# io.net
KiCad netlist of a schematic drawn in EAGLE
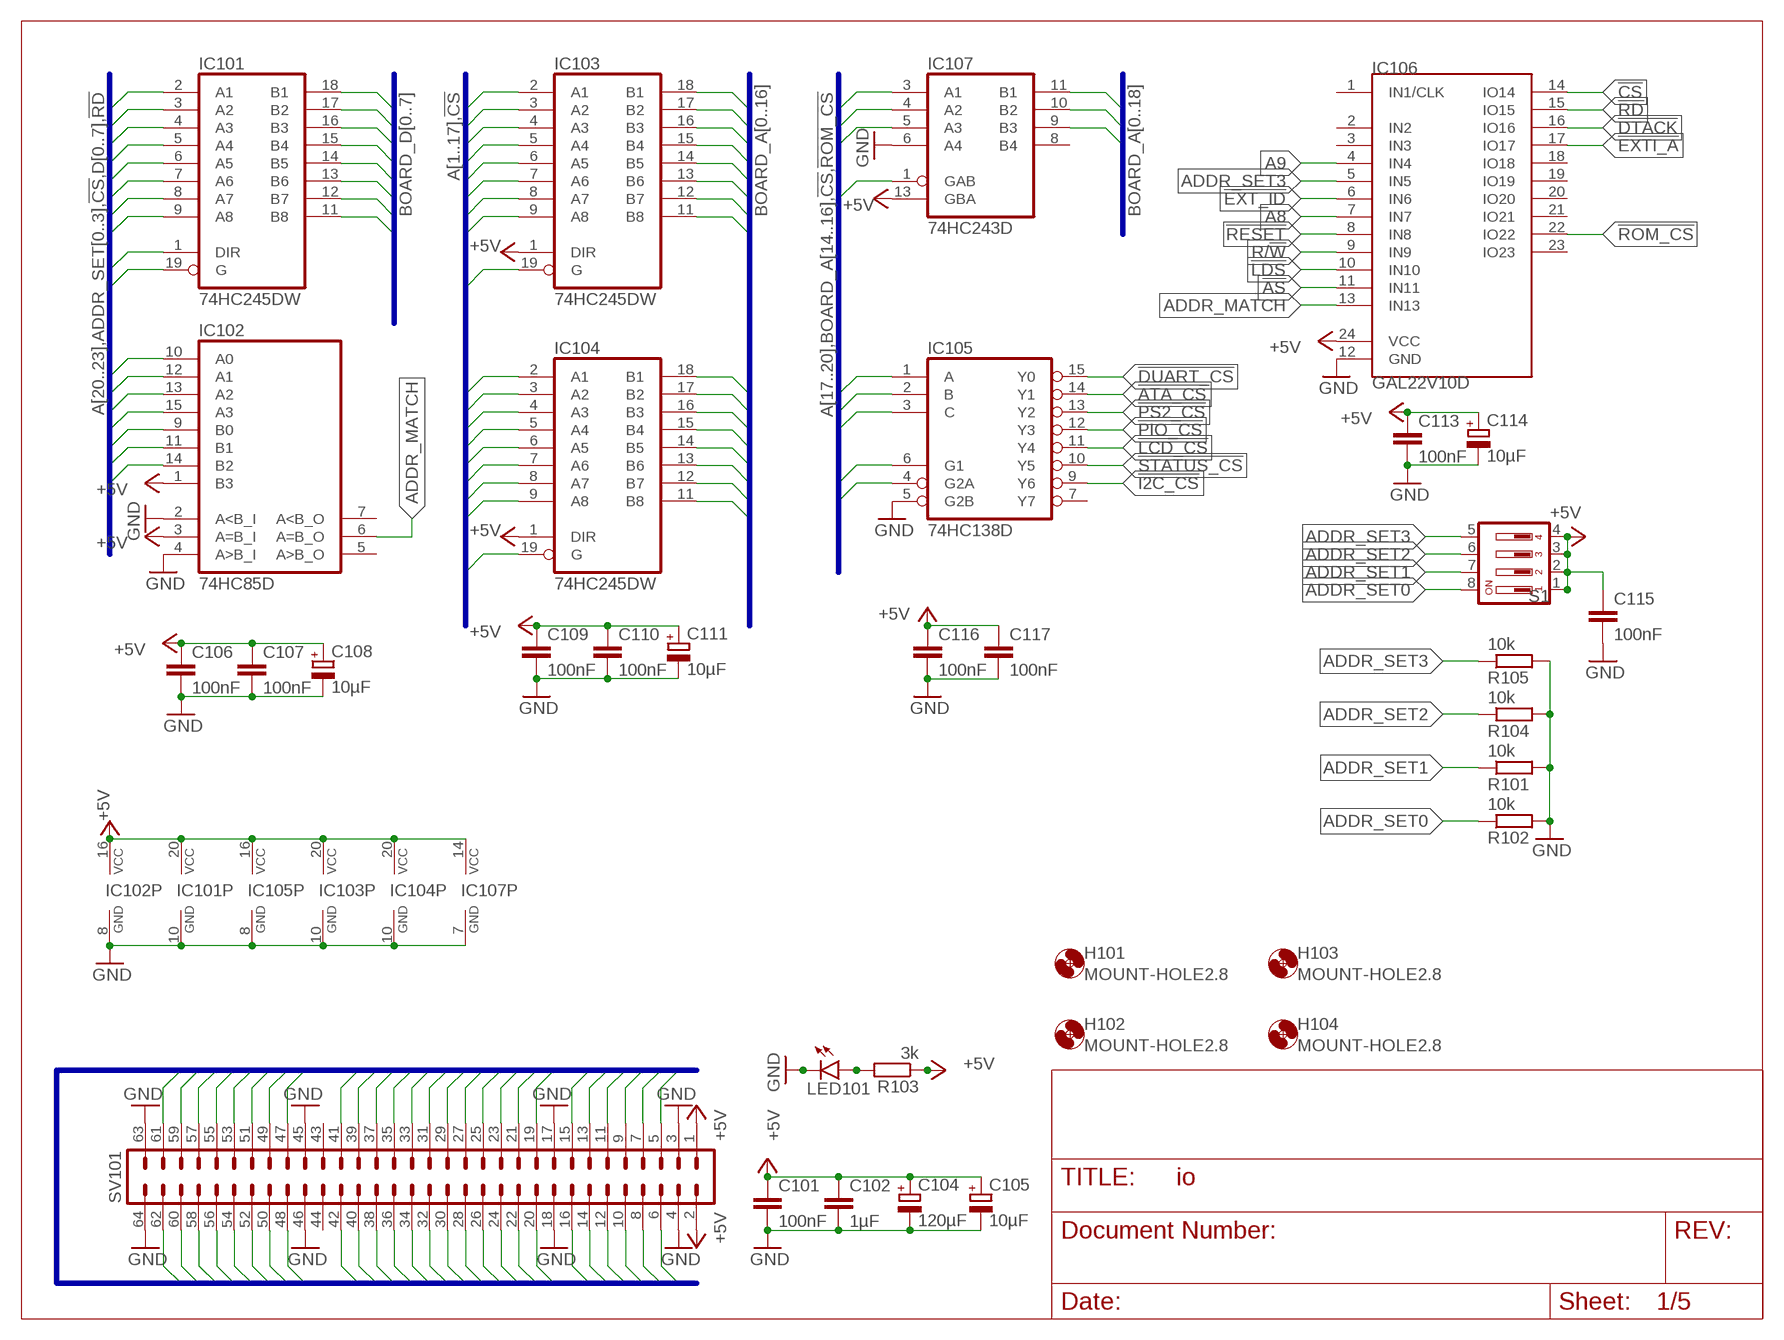
[diagram p0: schematic, sheet 1]
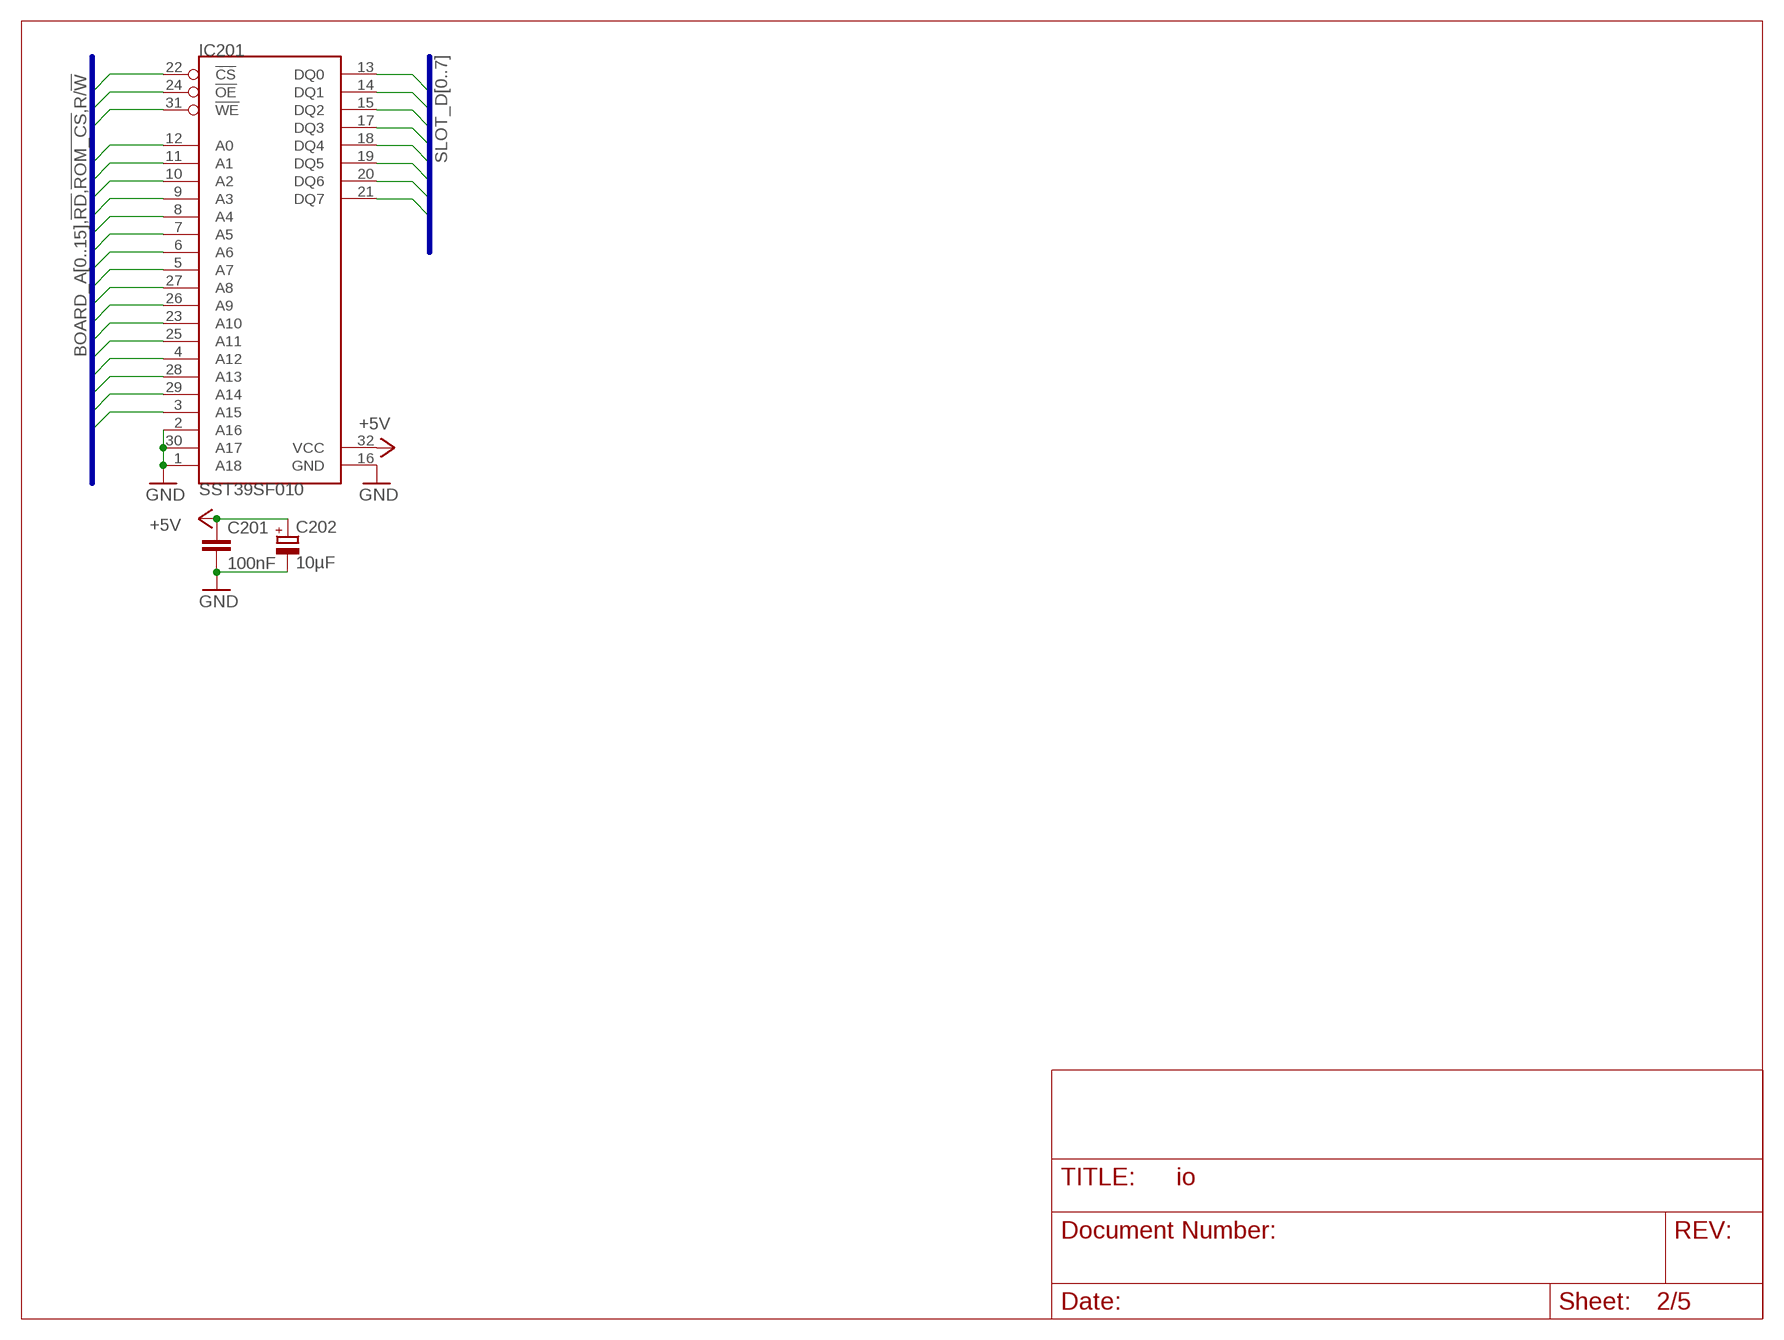
[diagram p1: schematic, sheet 2]
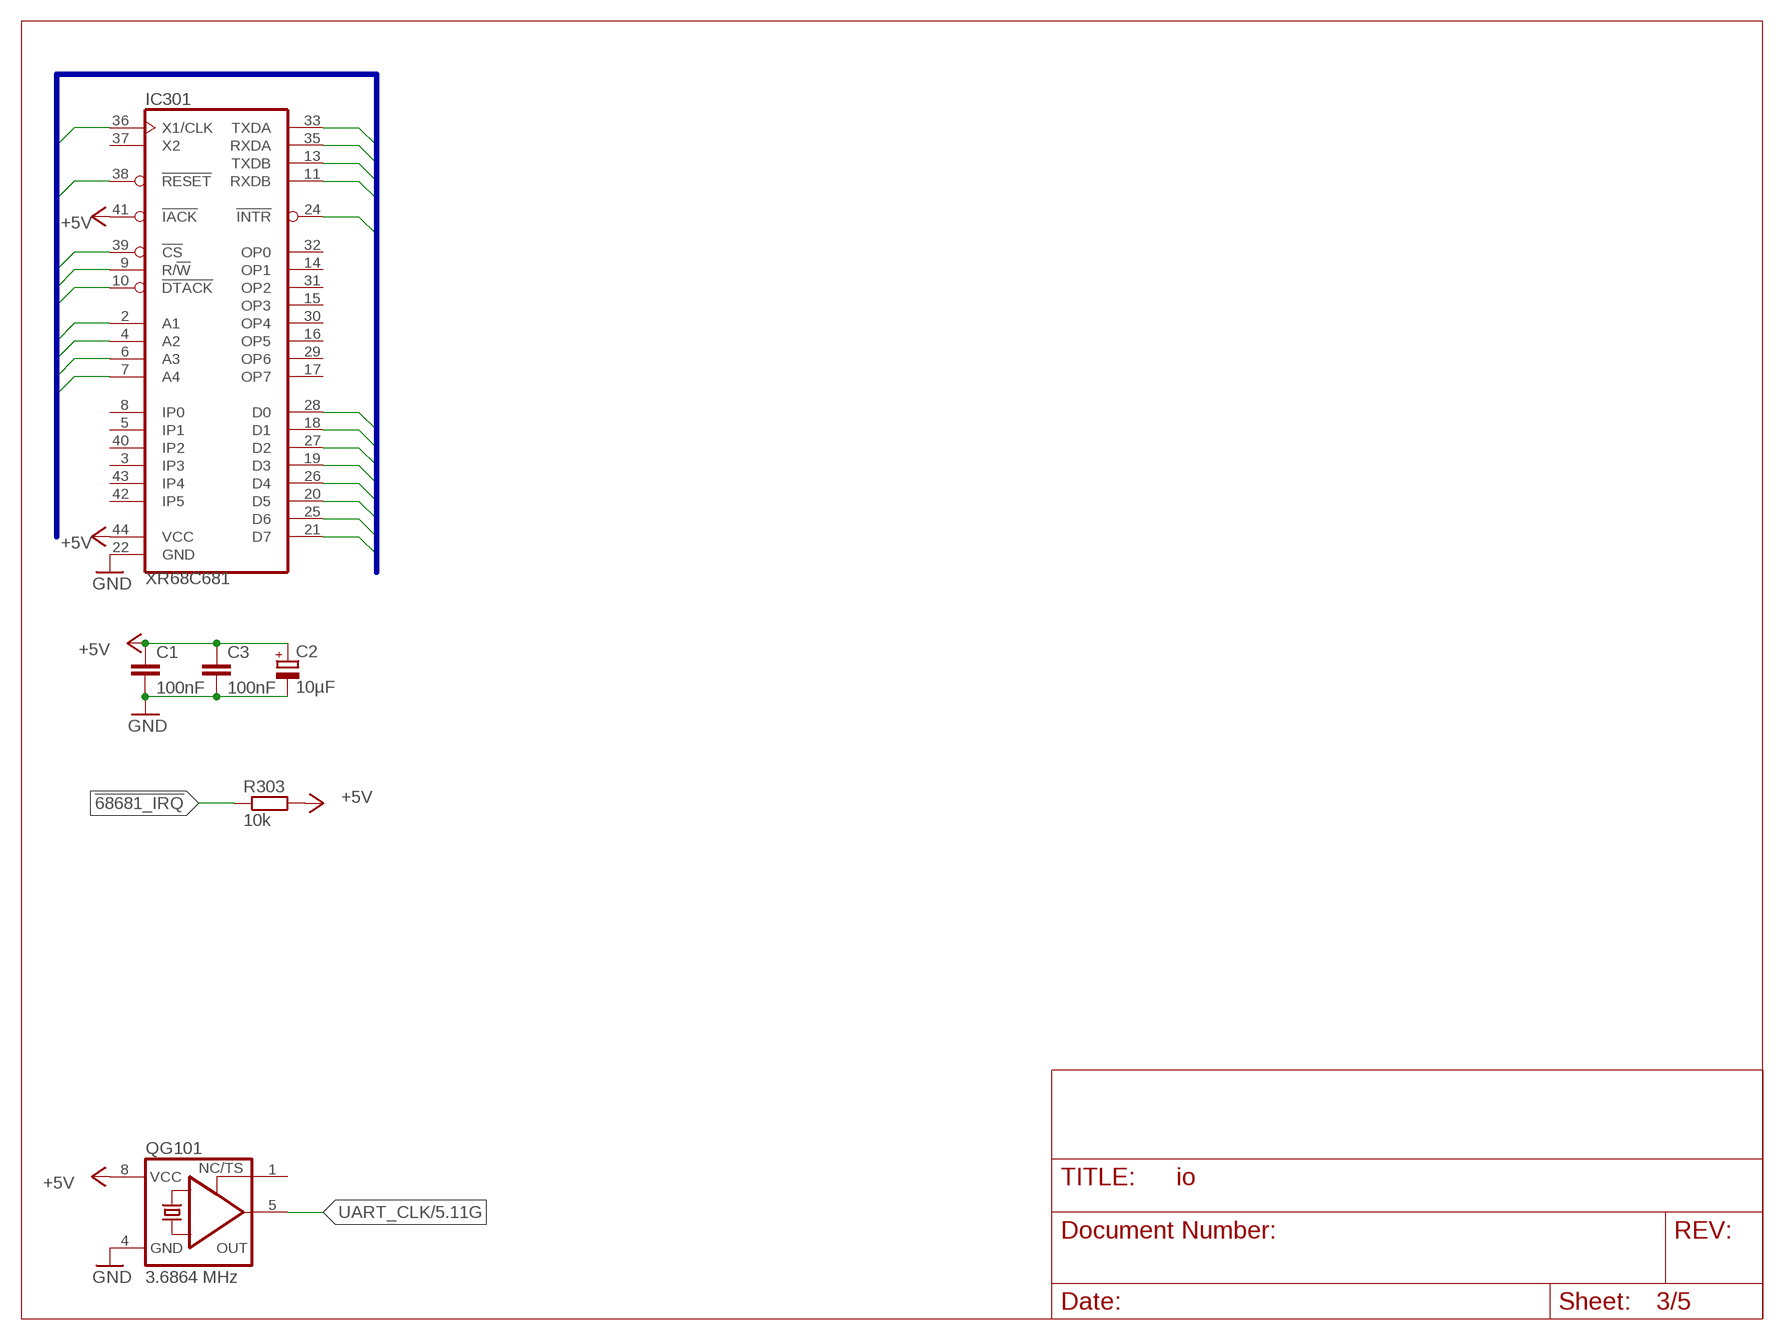
[diagram p2: schematic, sheet 3]
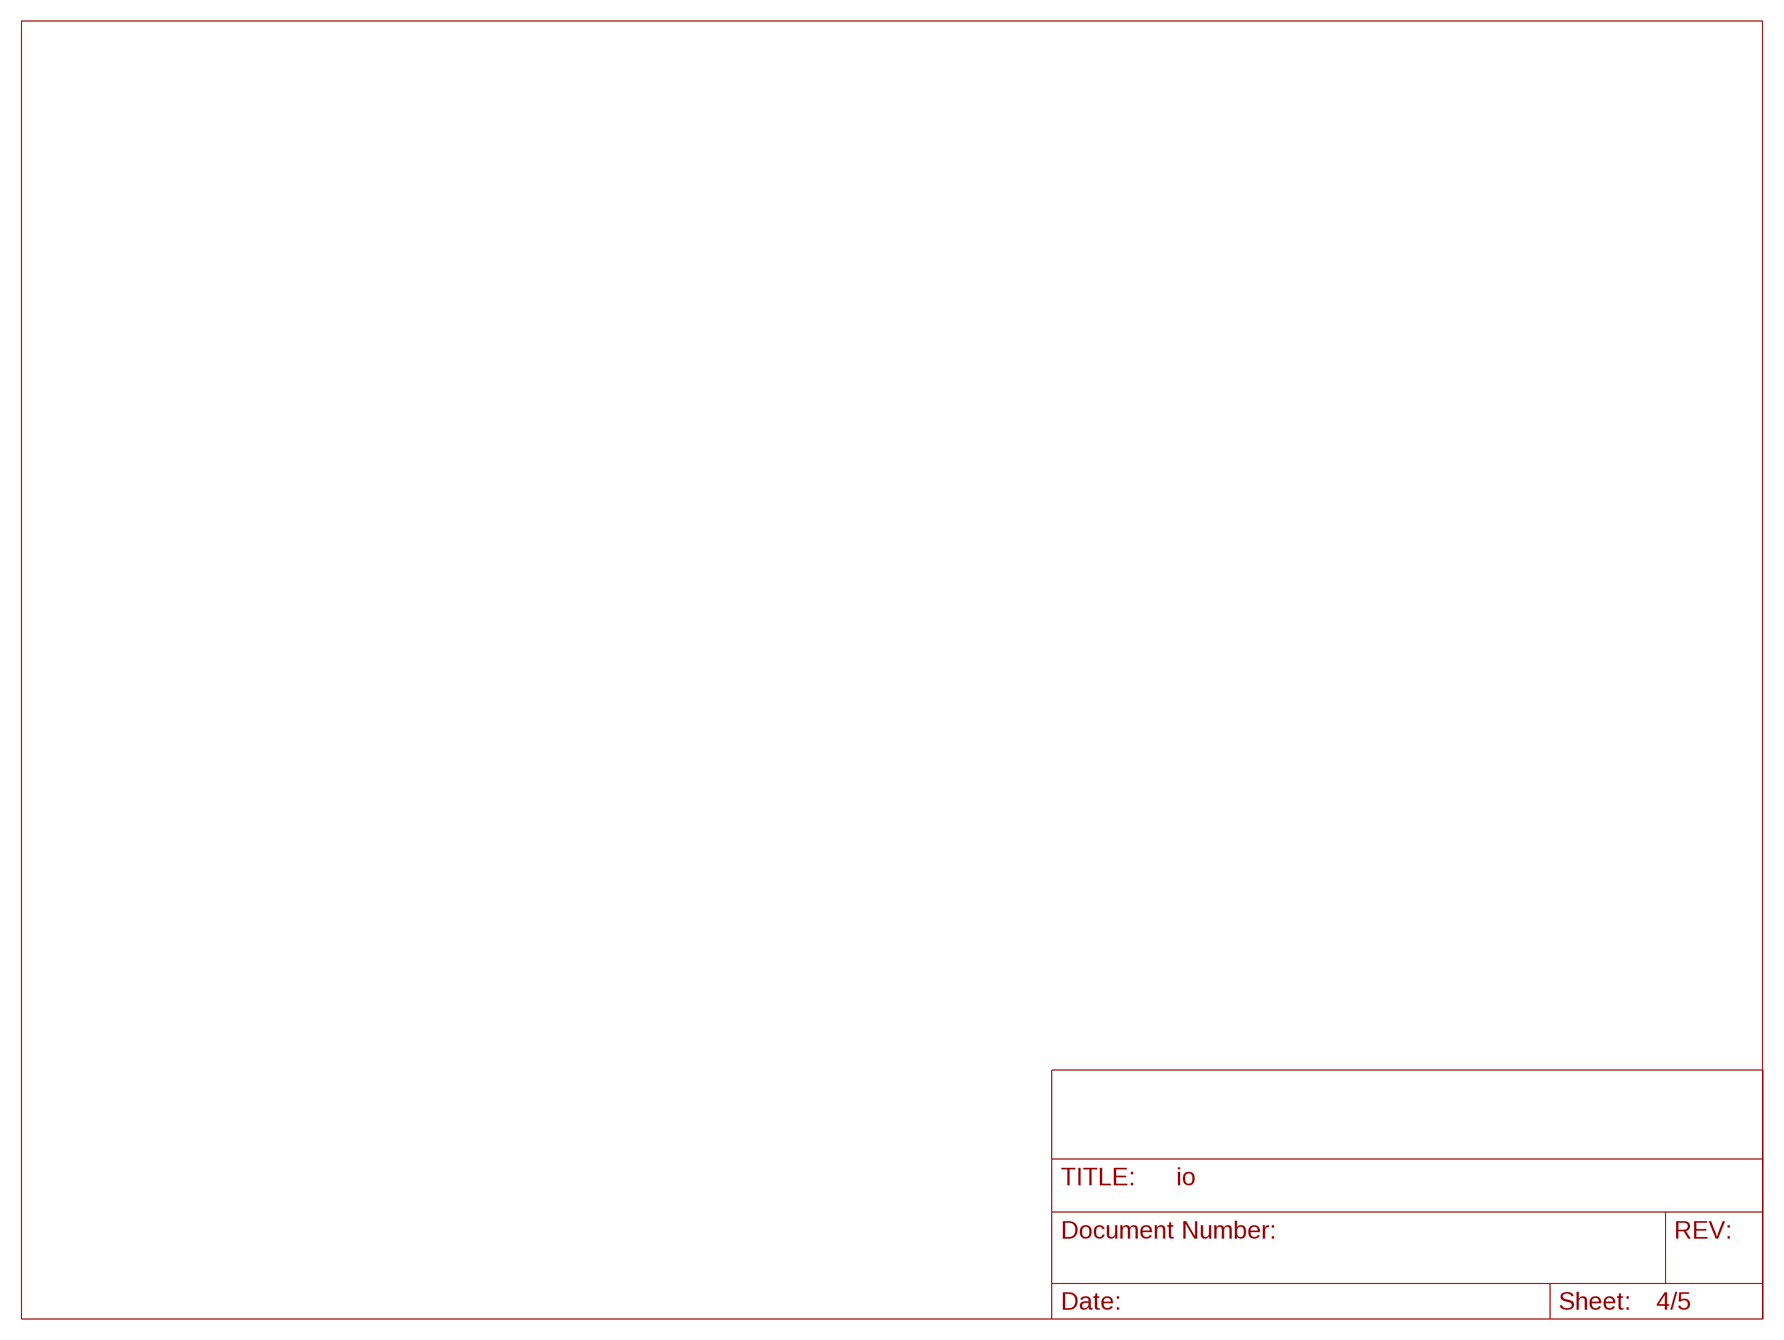
[diagram p3: schematic, sheet 4]
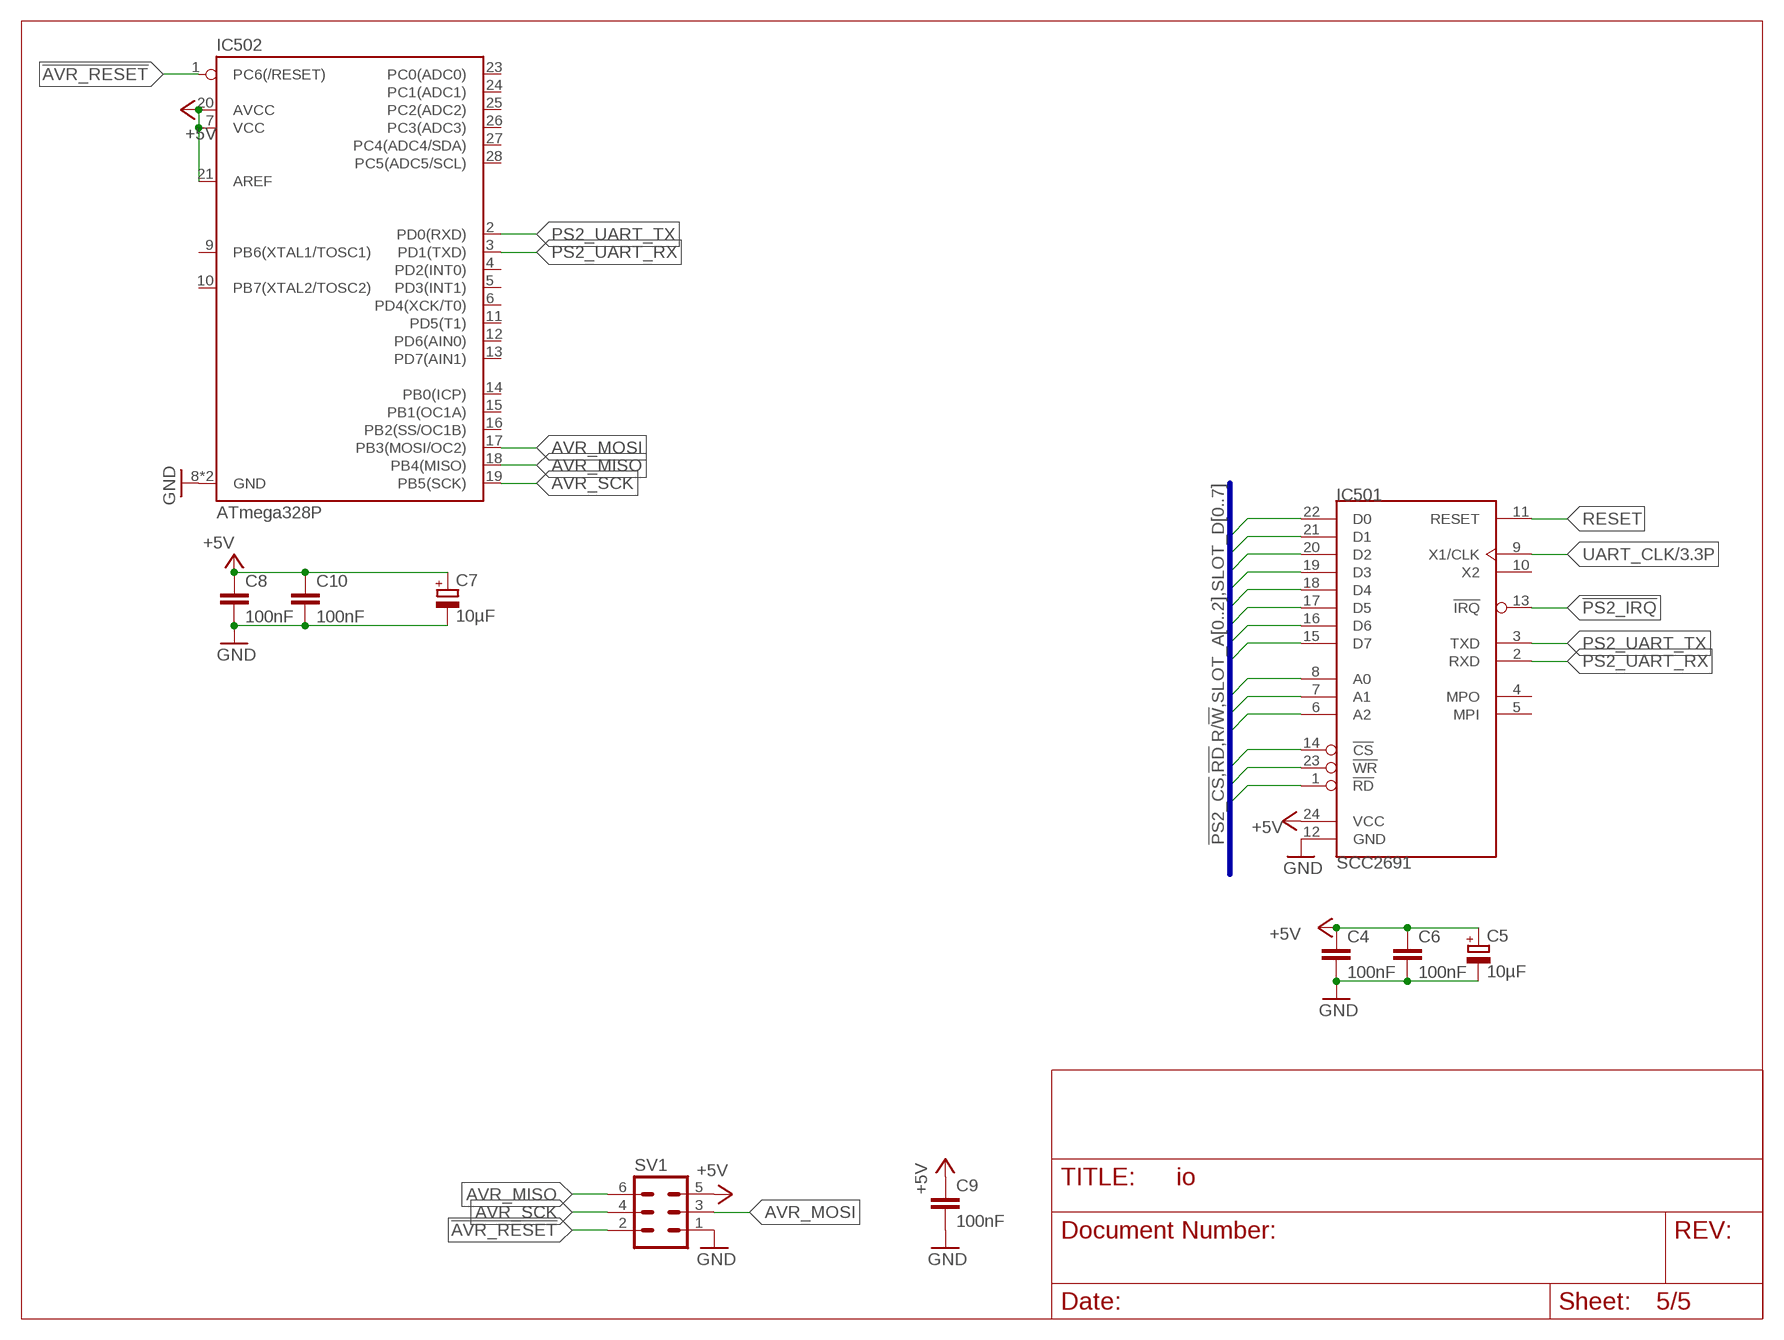
[diagram p4: schematic, sheet 5]

(export (version "E")
  (design (tool "Eeschema 10.0.6"))
  (components
    (comp (ref "C1")
      (value "100nF")
      (footprint "eagle-import:C0805")
      (libsource (lib "eagle-import") (part "C-EUC0805"))
    )
    (comp (ref "C2")
      (value "10µF")
      (footprint "eagle-import:SMC_B")
      (libsource (lib "eagle-import") (part "CPOL-EUSMCB"))
    )
    (comp (ref "C3")
      (value "100nF")
      (footprint "eagle-import:C0805")
      (libsource (lib "eagle-import") (part "C-EUC0805"))
    )
    (comp (ref "IC301")
      (value "XR68C681")
      (footprint "eagle-import:PLCC-S44")
      (libsource (lib "eagle-import") (part "MC68681PLCC44-SOCKET"))
    )
    (comp (ref "QG101")
      (value "3.6864 MHz")
      (footprint "eagle-import:DIL08S")
      (libsource (lib "eagle-import") (part "XO-8"))
    )
    (comp (ref "R303")
      (value "10k")
      (footprint "eagle-import:R2012")
      (libsource (lib "eagle-import") (part "R-EU_R2012"))
    )
    (comp (ref "C101")
      (value "100nF")
      (footprint "eagle-import:C0805")
      (libsource (lib "eagle-import") (part "C-EUC0805"))
    )
    (comp (ref "C102")
      (value "1µF")
      (footprint "eagle-import:C0805")
      (libsource (lib "eagle-import") (part "C-EUC0805"))
    )
    (comp (ref "C104")
      (value "120µF")
      (footprint "eagle-import:E2,5-7")
      (libsource (lib "eagle-import") (part "CPOL-EUE2.5-7"))
    )
    (comp (ref "C105")
      (value "10µF")
      (footprint "eagle-import:SMC_B")
      (libsource (lib "eagle-import") (part "CPOL-EUSMCB"))
    )
    (comp (ref "C106")
      (value "100nF")
      (footprint "eagle-import:C0805")
      (libsource (lib "eagle-import") (part "C-EUC0805"))
    )
    (comp (ref "C107")
      (value "100nF")
      (footprint "eagle-import:C0805")
      (libsource (lib "eagle-import") (part "C-EUC0805"))
    )
    (comp (ref "C108")
      (value "10µF")
      (footprint "eagle-import:SMC_B")
      (libsource (lib "eagle-import") (part "CPOL-EUSMCB"))
    )
    (comp (ref "C109")
      (value "100nF")
      (footprint "eagle-import:C0805")
      (libsource (lib "eagle-import") (part "C-EUC0805"))
    )
    (comp (ref "C110")
      (value "100nF")
      (footprint "eagle-import:C0805")
      (libsource (lib "eagle-import") (part "C-EUC0805"))
    )
    (comp (ref "C111")
      (value "10µF")
      (footprint "eagle-import:SMC_B")
      (libsource (lib "eagle-import") (part "CPOL-EUSMCB"))
    )
    (comp (ref "C113")
      (value "100nF")
      (footprint "eagle-import:C0805")
      (libsource (lib "eagle-import") (part "C-EUC0805"))
    )
    (comp (ref "C114")
      (value "10µF")
      (footprint "eagle-import:SMC_B")
      (libsource (lib "eagle-import") (part "CPOL-EUSMCB"))
    )
    (comp (ref "C115")
      (value "100nF")
      (footprint "eagle-import:C0805")
      (libsource (lib "eagle-import") (part "C-EUC0805"))
    )
    (comp (ref "C116")
      (value "100nF")
      (footprint "eagle-import:C0805")
      (libsource (lib "eagle-import") (part "C-EUC0805"))
    )
    (comp (ref "C117")
      (value "100nF")
      (footprint "eagle-import:C0805")
      (libsource (lib "eagle-import") (part "C-EUC0805"))
    )
    (comp (ref "H101")
      (value "MOUNT-HOLE2.8")
      (footprint "eagle-import:2,8")
      (libsource (lib "eagle-import") (part "MOUNT-HOLE2.8"))
    )
    (comp (ref "H102")
      (value "MOUNT-HOLE2.8")
      (footprint "eagle-import:2,8")
      (libsource (lib "eagle-import") (part "MOUNT-HOLE2.8"))
    )
    (comp (ref "H103")
      (value "MOUNT-HOLE2.8")
      (footprint "eagle-import:2,8")
      (libsource (lib "eagle-import") (part "MOUNT-HOLE2.8"))
    )
    (comp (ref "H104")
      (value "MOUNT-HOLE2.8")
      (footprint "eagle-import:2,8")
      (libsource (lib "eagle-import") (part "MOUNT-HOLE2.8"))
    )
    (comp (ref "IC101")
      (value "74HC245DW")
      (footprint "eagle-import:SO20W")
      (fields (field (name "MOUSER") "595-SN74HC245DWR"))
      (libsource (lib "eagle-import") (part "74245DWHC"))
    )
    (comp (ref "IC102")
      (value "74HC85D")
      (footprint "eagle-import:SO16")
      (fields (field (name "MOUSER") "771-74HC138D"))
      (libsource (lib "eagle-import") (part "7485DHC"))
    )
    (comp (ref "IC103")
      (value "74HC245DW")
      (footprint "eagle-import:SO20W")
      (fields (field (name "MOUSER") "595-SN74HC245DWR"))
      (libsource (lib "eagle-import") (part "74245DWHC"))
    )
    (comp (ref "IC104")
      (value "74HC245DW")
      (footprint "eagle-import:SO20W")
      (fields (field (name "MOUSER") "595-SN74HC245DWR"))
      (libsource (lib "eagle-import") (part "74245DWHC"))
    )
    (comp (ref "IC105")
      (value "74HC138D")
      (footprint "eagle-import:SO16")
      (fields (field (name "MOUSER") "771-74HC138D"))
      (libsource (lib "eagle-import") (part "74138DHC"))
    )
    (comp (ref "IC106")
      (value "GAL22V10D")
      (footprint "eagle-import:DIL24S")
      (libsource (lib "eagle-import") (part "GAL22V10DIP24"))
    )
    (comp (ref "IC107")
      (value "74HC243D")
      (footprint "eagle-import:SO14")
      (fields (field (name "MOUSER") "595-CD74HC243M96"))
      (libsource (lib "eagle-import") (part "74243DHC"))
    )
    (comp (ref "LED101")
      (value "LEDCHIPLED_1206")
      (footprint "eagle-import:CHIPLED_1206")
      (libsource (lib "eagle-import") (part "LEDCHIPLED_1206"))
    )
    (comp (ref "R101")
      (value "10k")
      (footprint "eagle-import:R2012")
      (libsource (lib "eagle-import") (part "R-EU_R2012"))
    )
    (comp (ref "R102")
      (value "10k")
      (footprint "eagle-import:R2012")
      (libsource (lib "eagle-import") (part "R-EU_R2012"))
    )
    (comp (ref "R103")
      (value "3k")
      (footprint "eagle-import:R2012")
      (libsource (lib "eagle-import") (part "R-EU_R2012"))
    )
    (comp (ref "R104")
      (value "10k")
      (footprint "eagle-import:R2012")
      (libsource (lib "eagle-import") (part "R-EU_R2012"))
    )
    (comp (ref "R105")
      (value "10k")
      (footprint "eagle-import:R2012")
      (libsource (lib "eagle-import") (part "R-EU_R2012"))
    )
    (comp (ref "S1")
      (value "DP04")
      (footprint "eagle-import:DP-04")
      (libsource (lib "eagle-import") (part "DP04"))
    )
    (comp (ref "SV101")
      (value "ML64L")
      (footprint "eagle-import:ML64L")
      (libsource (lib "eagle-import") (part "ML64L"))
    )
    (comp (ref "C201")
      (value "100nF")
      (footprint "eagle-import:C0805")
      (libsource (lib "eagle-import") (part "C-EUC0805"))
    )
    (comp (ref "C202")
      (value "10µF")
      (footprint "eagle-import:SMC_B")
      (libsource (lib "eagle-import") (part "CPOL-EUSMCB"))
    )
    (comp (ref "IC201")
      (value "SST39SF010")
      (footprint "eagle-import:PLCC-S32")
      (libsource (lib "eagle-import") (part "SST39SF0X0PLCC32-SOCKET"))
    )
    (comp (ref "C4")
      (value "100nF")
      (footprint "eagle-import:C0805")
      (libsource (lib "eagle-import") (part "C-EUC0805"))
    )
    (comp (ref "C5")
      (value "10µF")
      (footprint "eagle-import:SMC_B")
      (libsource (lib "eagle-import") (part "CPOL-EUSMCB"))
    )
    (comp (ref "C6")
      (value "100nF")
      (footprint "eagle-import:C0805")
      (libsource (lib "eagle-import") (part "C-EUC0805"))
    )
    (comp (ref "C7")
      (value "10µF")
      (footprint "eagle-import:SMC_B")
      (libsource (lib "eagle-import") (part "CPOL-EUSMCB"))
    )
    (comp (ref "C8")
      (value "100nF")
      (footprint "eagle-import:C0805")
      (libsource (lib "eagle-import") (part "C-EUC0805"))
    )
    (comp (ref "C9")
      (value "100nF")
      (footprint "eagle-import:C0805")
      (libsource (lib "eagle-import") (part "C-EUC0805"))
    )
    (comp (ref "C10")
      (value "100nF")
      (footprint "eagle-import:C0805")
      (libsource (lib "eagle-import") (part "C-EUC0805"))
    )
    (comp (ref "IC501")
      (value "SCC2691")
      (footprint "eagle-import:DIL24S")
      (libsource (lib "eagle-import") (part "SCC2691"))
    )
    (comp (ref "IC502")
      (value "ATmega328P")
      (footprint "eagle-import:DIP28")
      (libsource (lib "eagle-import") (part "ATMEGA328P_PDIP"))
    )
    (comp (ref "SV1")
      (value "ML6")
      (footprint "eagle-import:ML6")
      (libsource (lib "eagle-import") (part "ML6"))
    )
  )
  (nets
    (net (code "3") (name "+5V") (class "Default")
      (node (ref "C1") (pin "1") (pinfunction "1_1") (pintype "passive"))
      (node (ref "C10") (pin "1") (pinfunction "1_1") (pintype "passive"))
      (node (ref "C101") (pin "1") (pinfunction "1_1") (pintype "passive"))
      (node (ref "C102") (pin "1") (pinfunction "1_1") (pintype "passive"))
      (node (ref "C104") (pin "+") (pinfunction "+_+") (pintype "passive"))
      (node (ref "C105") (pin "+") (pinfunction "+_+") (pintype "passive"))
      (node (ref "C106") (pin "1") (pinfunction "1_1") (pintype "passive"))
      (node (ref "C107") (pin "1") (pinfunction "1_1") (pintype "passive"))
      (node (ref "C108") (pin "+") (pinfunction "+_+") (pintype "passive"))
      (node (ref "C109") (pin "1") (pinfunction "1_1") (pintype "passive"))
      (node (ref "C110") (pin "1") (pinfunction "1_1") (pintype "passive"))
      (node (ref "C111") (pin "+") (pinfunction "+_+") (pintype "passive"))
      (node (ref "C113") (pin "1") (pinfunction "1_1") (pintype "passive"))
      (node (ref "C114") (pin "+") (pinfunction "+_+") (pintype "passive"))
      (node (ref "C115") (pin "1") (pinfunction "1_1") (pintype "passive"))
      (node (ref "C116") (pin "1") (pinfunction "1_1") (pintype "passive"))
      (node (ref "C117") (pin "1") (pinfunction "1_1") (pintype "passive"))
      (node (ref "C2") (pin "+") (pinfunction "+_+") (pintype "passive"))
      (node (ref "C201") (pin "1") (pinfunction "1_1") (pintype "passive"))
      (node (ref "C202") (pin "+") (pinfunction "+_+") (pintype "passive"))
      (node (ref "C3") (pin "1") (pinfunction "1_1") (pintype "passive"))
      (node (ref "C4") (pin "1") (pinfunction "1_1") (pintype "passive"))
      (node (ref "C5") (pin "+") (pinfunction "+_+") (pintype "passive"))
      (node (ref "C6") (pin "1") (pinfunction "1_1") (pintype "passive"))
      (node (ref "C7") (pin "+") (pinfunction "+_+") (pintype "passive"))
      (node (ref "C8") (pin "1") (pinfunction "1_1") (pintype "passive"))
      (node (ref "C9") (pin "1") (pinfunction "1_1") (pintype "passive"))
      (node (ref "IC101") (pin "20") (pinfunction "VCC_20") (pintype "power_in"))
      (node (ref "IC102") (pin "1") (pinfunction "B3_1") (pintype "input"))
      (node (ref "IC102") (pin "16") (pinfunction "VCC_16") (pintype "power_in"))
      (node (ref "IC102") (pin "3") (pinfunction "A=B_I_3") (pintype "input"))
      (node (ref "IC103") (pin "1") (pinfunction "DIR_1") (pintype "input"))
      (node (ref "IC103") (pin "20") (pinfunction "VCC_20") (pintype "power_in"))
      (node (ref "IC104") (pin "1") (pinfunction "DIR_1") (pintype "input"))
      (node (ref "IC104") (pin "20") (pinfunction "VCC_20") (pintype "power_in"))
      (node (ref "IC105") (pin "16") (pinfunction "VCC_16") (pintype "power_in"))
      (node (ref "IC106") (pin "24") (pinfunction "VCC_24") (pintype "power_in"))
      (node (ref "IC107") (pin "13") (pinfunction "GBA_13") (pintype "input"))
      (node (ref "IC107") (pin "14") (pinfunction "VCC_14") (pintype "power_in"))
      (node (ref "IC201") (pin "32") (pinfunction "VCC_32") (pintype "power_in"))
      (node (ref "IC301") (pin "41") (pinfunction "~{IACK}_41") (pintype "input"))
      (node (ref "IC301") (pin "44") (pinfunction "VCC_44") (pintype "power_in"))
      (node (ref "IC501") (pin "24") (pinfunction "VCC_24") (pintype "power_in"))
      (node (ref "IC502") (pin "20") (pinfunction "AVCC_20") (pintype "bidirectional"))
      (node (ref "IC502") (pin "21") (pinfunction "AREF_21") (pintype "bidirectional"))
      (node (ref "IC502") (pin "7") (pinfunction "VCC_7") (pintype "bidirectional"))
      (node (ref "QG101") (pin "8") (pinfunction "VCC_8") (pintype "power_in"))
      (node (ref "R103") (pin "1") (pinfunction "1_1") (pintype "passive"))
      (node (ref "R303") (pin "2") (pinfunction "2_2") (pintype "passive"))
      (node (ref "S1") (pin "1") (pinfunction "1_1") (pintype "passive"))
      (node (ref "S1") (pin "2") (pinfunction "2_2") (pintype "passive"))
      (node (ref "S1") (pin "3") (pinfunction "3_3") (pintype "passive"))
      (node (ref "S1") (pin "4") (pinfunction "4_4") (pintype "passive"))
      (node (ref "SV1") (pin "5") (pinfunction "5_5") (pintype "passive"))
      (node (ref "SV101") (pin "1") (pinfunction "1_1") (pintype "passive"))
      (node (ref "SV101") (pin "2") (pinfunction "2_2") (pintype "passive"))
    )
    (net (code "13") (name "A1") (class "Default")
      (node (ref "IC103") (pin "2") (pinfunction "A1_2") (pintype "bidirectional"))
      (node (ref "SV101") (pin "20") (pinfunction "20_20") (pintype "passive"))
    )
    (net (code "14") (name "A2") (class "Default")
      (node (ref "IC103") (pin "3") (pinfunction "A2_3") (pintype "bidirectional"))
      (node (ref "SV101") (pin "22") (pinfunction "22_22") (pintype "passive"))
    )
    (net (code "15") (name "A3") (class "Default")
      (node (ref "IC103") (pin "4") (pinfunction "A3_4") (pintype "bidirectional"))
      (node (ref "SV101") (pin "19") (pinfunction "19_19") (pintype "passive"))
    )
    (net (code "16") (name "A4") (class "Default")
      (node (ref "IC103") (pin "5") (pinfunction "A4_5") (pintype "bidirectional"))
      (node (ref "SV101") (pin "24") (pinfunction "24_24") (pintype "passive"))
    )
    (net (code "17") (name "A5") (class "Default")
      (node (ref "IC103") (pin "6") (pinfunction "A5_6") (pintype "bidirectional"))
      (node (ref "SV101") (pin "21") (pinfunction "21_21") (pintype "passive"))
    )
    (net (code "18") (name "A6") (class "Default")
      (node (ref "IC103") (pin "7") (pinfunction "A6_7") (pintype "bidirectional"))
      (node (ref "SV101") (pin "23") (pinfunction "23_23") (pintype "passive"))
    )
    (net (code "19") (name "A7") (class "Default")
      (node (ref "IC103") (pin "8") (pinfunction "A7_8") (pintype "bidirectional"))
      (node (ref "SV101") (pin "26") (pinfunction "26_26") (pintype "passive"))
    )
    (net (code "20") (name "A8") (class "Default")
      (node (ref "IC103") (pin "9") (pinfunction "A8_9") (pintype "bidirectional"))
      (node (ref "IC106") (pin "7") (pinfunction "IN7_7") (pintype "input"))
      (node (ref "SV101") (pin "25") (pinfunction "25_25") (pintype "passive"))
    )
    (net (code "21") (name "A9") (class "Default")
      (node (ref "IC104") (pin "2") (pinfunction "A1_2") (pintype "bidirectional"))
      (node (ref "IC106") (pin "4") (pinfunction "IN4_4") (pintype "input"))
      (node (ref "SV101") (pin "28") (pinfunction "28_28") (pintype "passive"))
    )
    (net (code "22") (name "A10") (class "Default")
      (node (ref "IC104") (pin "3") (pinfunction "A2_3") (pintype "bidirectional"))
      (node (ref "SV101") (pin "27") (pinfunction "27_27") (pintype "passive"))
    )
    (net (code "23") (name "A11") (class "Default")
      (node (ref "IC104") (pin "4") (pinfunction "A3_4") (pintype "bidirectional"))
      (node (ref "SV101") (pin "30") (pinfunction "30_30") (pintype "passive"))
    )
    (net (code "24") (name "A12") (class "Default")
      (node (ref "IC104") (pin "5") (pinfunction "A4_5") (pintype "bidirectional"))
      (node (ref "SV101") (pin "29") (pinfunction "29_29") (pintype "passive"))
    )
    (net (code "25") (name "A13") (class "Default")
      (node (ref "IC104") (pin "6") (pinfunction "A5_6") (pintype "bidirectional"))
      (node (ref "SV101") (pin "31") (pinfunction "31_31") (pintype "passive"))
    )
    (net (code "26") (name "A14") (class "Default")
      (node (ref "IC104") (pin "7") (pinfunction "A6_7") (pintype "bidirectional"))
      (node (ref "SV101") (pin "32") (pinfunction "32_32") (pintype "passive"))
    )
    (net (code "27") (name "A15") (class "Default")
      (node (ref "IC104") (pin "8") (pinfunction "A7_8") (pintype "bidirectional"))
      (node (ref "SV101") (pin "33") (pinfunction "33_33") (pintype "passive"))
    )
    (net (code "28") (name "A16") (class "Default")
      (node (ref "IC104") (pin "9") (pinfunction "A8_9") (pintype "bidirectional"))
      (node (ref "SV101") (pin "34") (pinfunction "34_34") (pintype "passive"))
    )
    (net (code "29") (name "A17") (class "Default")
      (node (ref "IC107") (pin "3") (pinfunction "A1_3") (pintype "bidirectional"))
      (node (ref "SV101") (pin "36") (pinfunction "36_36") (pintype "passive"))
    )
    (net (code "30") (name "A18") (class "Default")
      (node (ref "IC107") (pin "4") (pinfunction "A2_4") (pintype "bidirectional"))
      (node (ref "SV101") (pin "35") (pinfunction "35_35") (pintype "passive"))
    )
    (net (code "31") (name "A19") (class "Default")
      (node (ref "IC107") (pin "5") (pinfunction "A3_5") (pintype "bidirectional"))
      (node (ref "SV101") (pin "38") (pinfunction "38_38") (pintype "passive"))
    )
    (net (code "32") (name "A20") (class "Default")
      (node (ref "IC102") (pin "10") (pinfunction "A0_10") (pintype "input"))
      (node (ref "SV101") (pin "37") (pinfunction "37_37") (pintype "passive"))
    )
    (net (code "33") (name "A21") (class "Default")
      (node (ref "IC102") (pin "12") (pinfunction "A1_12") (pintype "input"))
      (node (ref "SV101") (pin "40") (pinfunction "40_40") (pintype "passive"))
    )
    (net (code "34") (name "A22") (class "Default")
      (node (ref "IC102") (pin "13") (pinfunction "A2_13") (pintype "input"))
      (node (ref "SV101") (pin "39") (pinfunction "39_39") (pintype "passive"))
    )
    (net (code "35") (name "A23") (class "Default")
      (node (ref "IC102") (pin "15") (pinfunction "A3_15") (pintype "input"))
      (node (ref "SV101") (pin "42") (pinfunction "42_42") (pintype "passive"))
    )
    (net (code "36") (name "ADDR_MATCH") (class "Default")
      (node (ref "IC102") (pin "6") (pinfunction "A=B_O_6") (pintype "output"))
      (node (ref "IC106") (pin "13") (pinfunction "IN13_13") (pintype "input"))
    )
    (net (code "37") (name "ADDR_SET0") (class "Default")
      (node (ref "IC102") (pin "9") (pinfunction "B0_9") (pintype "input"))
      (node (ref "R102") (pin "1") (pinfunction "1_1") (pintype "passive"))
      (node (ref "S1") (pin "8") (pinfunction "8_8") (pintype "passive"))
    )
    (net (code "38") (name "ADDR_SET1") (class "Default")
      (node (ref "IC102") (pin "11") (pinfunction "B1_11") (pintype "input"))
      (node (ref "R101") (pin "1") (pinfunction "1_1") (pintype "passive"))
      (node (ref "S1") (pin "7") (pinfunction "7_7") (pintype "passive"))
    )
    (net (code "39") (name "ADDR_SET2") (class "Default")
      (node (ref "IC102") (pin "14") (pinfunction "B2_14") (pintype "input"))
      (node (ref "R104") (pin "1") (pinfunction "1_1") (pintype "passive"))
      (node (ref "S1") (pin "6") (pinfunction "6_6") (pintype "passive"))
    )
    (net (code "40") (name "ADDR_SET3") (class "Default")
      (node (ref "IC106") (pin "5") (pinfunction "IN5_5") (pintype "input"))
      (node (ref "R105") (pin "1") (pinfunction "1_1") (pintype "passive"))
      (node (ref "S1") (pin "5") (pinfunction "5_5") (pintype "passive"))
    )
    (net (code "41") (name "AVR_MISO") (class "Default")
      (node (ref "IC502") (pin "18") (pinfunction "PB4(MISO)_18") (pintype "bidirectional"))
      (node (ref "SV1") (pin "6") (pinfunction "6_6") (pintype "passive"))
    )
    (net (code "42") (name "AVR_MOSI") (class "Default")
      (node (ref "IC502") (pin "17") (pinfunction "PB3(MOSI/OC2)_17") (pintype "bidirectional"))
      (node (ref "SV1") (pin "3") (pinfunction "3_3") (pintype "passive"))
    )
    (net (code "43") (name "AVR_SCK") (class "Default")
      (node (ref "IC502") (pin "19") (pinfunction "PB5(SCK)_19") (pintype "bidirectional"))
      (node (ref "SV1") (pin "4") (pinfunction "4_4") (pintype "passive"))
    )
    (net (code "44") (name "BOARD_A0") (class "Default")
      (node (ref "IC103") (pin "18") (pinfunction "B1_18") (pintype "bidirectional"))
      (node (ref "IC201") (pin "12") (pinfunction "A0_12") (pintype "input"))
      (node (ref "IC301") (pin "2") (pinfunction "A1_2") (pintype "input"))
    )
    (net (code "45") (name "BOARD_A1") (class "Default")
      (node (ref "IC103") (pin "17") (pinfunction "B2_17") (pintype "bidirectional"))
      (node (ref "IC201") (pin "11") (pinfunction "A1_11") (pintype "input"))
      (node (ref "IC301") (pin "4") (pinfunction "A2_4") (pintype "input"))
    )
    (net (code "46") (name "BOARD_A2") (class "Default")
      (node (ref "IC103") (pin "16") (pinfunction "B3_16") (pintype "bidirectional"))
      (node (ref "IC201") (pin "10") (pinfunction "A2_10") (pintype "input"))
      (node (ref "IC301") (pin "6") (pinfunction "A3_6") (pintype "input"))
    )
    (net (code "47") (name "BOARD_A3") (class "Default")
      (node (ref "IC103") (pin "15") (pinfunction "B4_15") (pintype "bidirectional"))
      (node (ref "IC201") (pin "9") (pinfunction "A3_9") (pintype "input"))
      (node (ref "IC301") (pin "7") (pinfunction "A4_7") (pintype "input"))
    )
    (net (code "48") (name "BOARD_A4") (class "Default")
      (node (ref "IC103") (pin "14") (pinfunction "B5_14") (pintype "bidirectional"))
      (node (ref "IC201") (pin "8") (pinfunction "A4_8") (pintype "input"))
    )
    (net (code "49") (name "BOARD_A5") (class "Default")
      (node (ref "IC103") (pin "13") (pinfunction "B6_13") (pintype "bidirectional"))
      (node (ref "IC201") (pin "7") (pinfunction "A5_7") (pintype "input"))
    )
    (net (code "50") (name "BOARD_A6") (class "Default")
      (node (ref "IC103") (pin "12") (pinfunction "B7_12") (pintype "bidirectional"))
      (node (ref "IC201") (pin "6") (pinfunction "A6_6") (pintype "input"))
    )
    (net (code "51") (name "BOARD_A7") (class "Default")
      (node (ref "IC103") (pin "11") (pinfunction "B8_11") (pintype "bidirectional"))
      (node (ref "IC201") (pin "5") (pinfunction "A7_5") (pintype "input"))
    )
    (net (code "52") (name "BOARD_A8") (class "Default")
      (node (ref "IC104") (pin "18") (pinfunction "B1_18") (pintype "bidirectional"))
      (node (ref "IC201") (pin "27") (pinfunction "A8_27") (pintype "input"))
    )
    (net (code "53") (name "BOARD_A9") (class "Default")
      (node (ref "IC104") (pin "17") (pinfunction "B2_17") (pintype "bidirectional"))
      (node (ref "IC201") (pin "26") (pinfunction "A9_26") (pintype "input"))
    )
    (net (code "54") (name "BOARD_A10") (class "Default")
      (node (ref "IC104") (pin "16") (pinfunction "B3_16") (pintype "bidirectional"))
      (node (ref "IC201") (pin "23") (pinfunction "A10_23") (pintype "input"))
    )
    (net (code "55") (name "BOARD_A11") (class "Default")
      (node (ref "IC104") (pin "15") (pinfunction "B4_15") (pintype "bidirectional"))
      (node (ref "IC201") (pin "25") (pinfunction "A11_25") (pintype "input"))
    )
    (net (code "56") (name "BOARD_A12") (class "Default")
      (node (ref "IC104") (pin "14") (pinfunction "B5_14") (pintype "bidirectional"))
      (node (ref "IC201") (pin "4") (pinfunction "A12_4") (pintype "input"))
    )
    (net (code "57") (name "BOARD_A13") (class "Default")
      (node (ref "IC104") (pin "13") (pinfunction "B6_13") (pintype "bidirectional"))
      (node (ref "IC201") (pin "28") (pinfunction "A13_28") (pintype "input"))
    )
    (net (code "58") (name "BOARD_A14") (class "Default")
      (node (ref "IC104") (pin "12") (pinfunction "B7_12") (pintype "bidirectional"))
      (node (ref "IC105") (pin "1") (pinfunction "A_1") (pintype "input"))
      (node (ref "IC201") (pin "29") (pinfunction "A14_29") (pintype "input"))
    )
    (net (code "59") (name "BOARD_A15") (class "Default")
      (node (ref "IC104") (pin "11") (pinfunction "B8_11") (pintype "bidirectional"))
      (node (ref "IC105") (pin "2") (pinfunction "B_2") (pintype "input"))
      (node (ref "IC201") (pin "3") (pinfunction "A15_3") (pintype "input"))
    )
    (net (code "60") (name "BOARD_A16") (class "Default")
      (node (ref "IC105") (pin "3") (pinfunction "C_3") (pintype "input"))
      (node (ref "IC107") (pin "11") (pinfunction "B1_11") (pintype "bidirectional"))
    )
    (net (code "61") (name "BOARD_D0") (class "Default")
      (node (ref "IC101") (pin "18") (pinfunction "B1_18") (pintype "bidirectional"))
      (node (ref "IC301") (pin "28") (pinfunction "D0_28") (pintype "bidirectional"))
    )
    (net (code "62") (name "BOARD_D1") (class "Default")
      (node (ref "IC101") (pin "17") (pinfunction "B2_17") (pintype "bidirectional"))
      (node (ref "IC301") (pin "18") (pinfunction "D1_18") (pintype "bidirectional"))
    )
    (net (code "63") (name "BOARD_D2") (class "Default")
      (node (ref "IC101") (pin "16") (pinfunction "B3_16") (pintype "bidirectional"))
      (node (ref "IC301") (pin "27") (pinfunction "D2_27") (pintype "bidirectional"))
    )
    (net (code "64") (name "BOARD_D3") (class "Default")
      (node (ref "IC101") (pin "15") (pinfunction "B4_15") (pintype "bidirectional"))
      (node (ref "IC301") (pin "19") (pinfunction "D3_19") (pintype "bidirectional"))
    )
    (net (code "65") (name "BOARD_D4") (class "Default")
      (node (ref "IC101") (pin "14") (pinfunction "B5_14") (pintype "bidirectional"))
      (node (ref "IC301") (pin "26") (pinfunction "D4_26") (pintype "bidirectional"))
    )
    (net (code "66") (name "BOARD_D5") (class "Default")
      (node (ref "IC101") (pin "13") (pinfunction "B6_13") (pintype "bidirectional"))
      (node (ref "IC301") (pin "20") (pinfunction "D5_20") (pintype "bidirectional"))
    )
    (net (code "67") (name "BOARD_D6") (class "Default")
      (node (ref "IC101") (pin "12") (pinfunction "B7_12") (pintype "bidirectional"))
      (node (ref "IC301") (pin "25") (pinfunction "D6_25") (pintype "bidirectional"))
    )
    (net (code "68") (name "BOARD_D7") (class "Default")
      (node (ref "IC101") (pin "11") (pinfunction "B8_11") (pintype "bidirectional"))
      (node (ref "IC301") (pin "21") (pinfunction "D7_21") (pintype "bidirectional"))
    )
    (net (code "69") (name "D0") (class "Default")
      (node (ref "IC101") (pin "2") (pinfunction "A1_2") (pintype "bidirectional"))
      (node (ref "SV101") (pin "62") (pinfunction "62_62") (pintype "passive"))
    )
    (net (code "70") (name "D1") (class "Default")
      (node (ref "IC101") (pin "3") (pinfunction "A2_3") (pintype "bidirectional"))
      (node (ref "SV101") (pin "60") (pinfunction "60_60") (pintype "passive"))
    )
    (net (code "71") (name "D2") (class "Default")
      (node (ref "IC101") (pin "4") (pinfunction "A3_4") (pintype "bidirectional"))
      (node (ref "SV101") (pin "58") (pinfunction "58_58") (pintype "passive"))
    )
    (net (code "72") (name "D3") (class "Default")
      (node (ref "IC101") (pin "5") (pinfunction "A4_5") (pintype "bidirectional"))
      (node (ref "SV101") (pin "56") (pinfunction "56_56") (pintype "passive"))
    )
    (net (code "73") (name "D4") (class "Default")
      (node (ref "IC101") (pin "6") (pinfunction "A5_6") (pintype "bidirectional"))
      (node (ref "SV101") (pin "54") (pinfunction "54_54") (pintype "passive"))
    )
    (net (code "74") (name "D5") (class "Default")
      (node (ref "IC101") (pin "7") (pinfunction "A6_7") (pintype "bidirectional"))
      (node (ref "SV101") (pin "52") (pinfunction "52_52") (pintype "passive"))
    )
    (net (code "75") (name "D6") (class "Default")
      (node (ref "IC101") (pin "8") (pinfunction "A7_8") (pintype "bidirectional"))
      (node (ref "SV101") (pin "50") (pinfunction "50_50") (pintype "passive"))
    )
    (net (code "76") (name "D7") (class "Default")
      (node (ref "IC101") (pin "9") (pinfunction "A8_9") (pintype "bidirectional"))
      (node (ref "SV101") (pin "48") (pinfunction "48_48") (pintype "passive"))
    )
    (net (code "77") (name "GND") (class "Default")
      (node (ref "C1") (pin "2") (pinfunction "2_2") (pintype "passive"))
      (node (ref "C10") (pin "2") (pinfunction "2_2") (pintype "passive"))
      (node (ref "C101") (pin "2") (pinfunction "2_2") (pintype "passive"))
      (node (ref "C102") (pin "2") (pinfunction "2_2") (pintype "passive"))
      (node (ref "C104") (pin "-") (pinfunction "-_-") (pintype "passive"))
      (node (ref "C105") (pin "-") (pinfunction "-_-") (pintype "passive"))
      (node (ref "C106") (pin "2") (pinfunction "2_2") (pintype "passive"))
      (node (ref "C107") (pin "2") (pinfunction "2_2") (pintype "passive"))
      (node (ref "C108") (pin "-") (pinfunction "-_-") (pintype "passive"))
      (node (ref "C109") (pin "2") (pinfunction "2_2") (pintype "passive"))
      (node (ref "C110") (pin "2") (pinfunction "2_2") (pintype "passive"))
      (node (ref "C111") (pin "-") (pinfunction "-_-") (pintype "passive"))
      (node (ref "C113") (pin "2") (pinfunction "2_2") (pintype "passive"))
      (node (ref "C114") (pin "-") (pinfunction "-_-") (pintype "passive"))
      (node (ref "C115") (pin "2") (pinfunction "2_2") (pintype "passive"))
      (node (ref "C116") (pin "2") (pinfunction "2_2") (pintype "passive"))
      (node (ref "C117") (pin "2") (pinfunction "2_2") (pintype "passive"))
      (node (ref "C2") (pin "-") (pinfunction "-_-") (pintype "passive"))
      (node (ref "C201") (pin "2") (pinfunction "2_2") (pintype "passive"))
      (node (ref "C202") (pin "-") (pinfunction "-_-") (pintype "passive"))
      (node (ref "C3") (pin "2") (pinfunction "2_2") (pintype "passive"))
      (node (ref "C4") (pin "2") (pinfunction "2_2") (pintype "passive"))
      (node (ref "C5") (pin "-") (pinfunction "-_-") (pintype "passive"))
      (node (ref "C6") (pin "2") (pinfunction "2_2") (pintype "passive"))
      (node (ref "C7") (pin "-") (pinfunction "-_-") (pintype "passive"))
      (node (ref "C8") (pin "2") (pinfunction "2_2") (pintype "passive"))
      (node (ref "C9") (pin "2") (pinfunction "2_2") (pintype "passive"))
      (node (ref "IC101") (pin "10") (pinfunction "GND_10") (pintype "power_in"))
      (node (ref "IC102") (pin "2") (pinfunction "A<B_I_2") (pintype "input"))
      (node (ref "IC102") (pin "4") (pinfunction "A>B_I_4") (pintype "input"))
      (node (ref "IC102") (pin "8") (pinfunction "GND_8") (pintype "power_in"))
      (node (ref "IC103") (pin "10") (pinfunction "GND_10") (pintype "power_in"))
      (node (ref "IC104") (pin "10") (pinfunction "GND_10") (pintype "power_in"))
      (node (ref "IC105") (pin "5") (pinfunction "G2B_5") (pintype "input"))
      (node (ref "IC105") (pin "8") (pinfunction "GND_8") (pintype "power_in"))
      (node (ref "IC106") (pin "12") (pinfunction "GND_12") (pintype "power_in"))
      (node (ref "IC107") (pin "6") (pinfunction "A4_6") (pintype "bidirectional"))
      (node (ref "IC107") (pin "7") (pinfunction "GND_7") (pintype "power_in"))
      (node (ref "IC201") (pin "1") (pinfunction "A18_1") (pintype "input"))
      (node (ref "IC201") (pin "16") (pinfunction "GND_16") (pintype "power_in"))
      (node (ref "IC201") (pin "2") (pinfunction "A16_2") (pintype "input"))
      (node (ref "IC201") (pin "30") (pinfunction "A17_30") (pintype "input"))
      (node (ref "IC301") (pin "22") (pinfunction "GND_22") (pintype "power_in"))
      (node (ref "IC501") (pin "12") (pinfunction "GND_12") (pintype "power_in"))
      (node (ref "IC502") (pin "22") (pinfunction "GND_22") (pintype "bidirectional"))
      (node (ref "IC502") (pin "8") (pinfunction "GND_8") (pintype "bidirectional"))
      (node (ref "LED101") (pin "C") (pinfunction "C_C") (pintype "passive"))
      (node (ref "QG101") (pin "4") (pinfunction "GND_4") (pintype "power_in"))
      (node (ref "R101") (pin "2") (pinfunction "2_2") (pintype "passive"))
      (node (ref "R102") (pin "2") (pinfunction "2_2") (pintype "passive"))
      (node (ref "R104") (pin "2") (pinfunction "2_2") (pintype "passive"))
      (node (ref "R105") (pin "2") (pinfunction "2_2") (pintype "passive"))
      (node (ref "SV1") (pin "1") (pinfunction "1_1") (pintype "passive"))
      (node (ref "SV101") (pin "17") (pinfunction "17_17") (pintype "passive"))
      (node (ref "SV101") (pin "18") (pinfunction "18_18") (pintype "passive"))
      (node (ref "SV101") (pin "3") (pinfunction "3_3") (pintype "passive"))
      (node (ref "SV101") (pin "4") (pinfunction "4_4") (pintype "passive"))
      (node (ref "SV101") (pin "45") (pinfunction "45_45") (pintype "passive"))
      (node (ref "SV101") (pin "46") (pinfunction "46_46") (pintype "passive"))
      (node (ref "SV101") (pin "63") (pinfunction "63_63") (pintype "passive"))
      (node (ref "SV101") (pin "64") (pinfunction "64_64") (pintype "passive"))
    )
    (net (code "78") (name "Net-(LED101-PadA)") (class "Default")
      (node (ref "LED101") (pin "A") (pinfunction "A_A") (pintype "passive"))
      (node (ref "R103") (pin "2") (pinfunction "2_2") (pintype "passive"))
    )
    (net (code "79") (name "PS2_UART_RX") (class "Default")
      (node (ref "IC501") (pin "2") (pinfunction "RXD_2") (pintype "input"))
      (node (ref "IC502") (pin "3") (pinfunction "PD1(TXD)_3") (pintype "bidirectional"))
    )
    (net (code "80") (name "PS2_UART_TX") (class "Default")
      (node (ref "IC501") (pin "3") (pinfunction "TXD_3") (pintype "output"))
      (node (ref "IC502") (pin "2") (pinfunction "PD0(RXD)_2") (pintype "bidirectional"))
    )
    (net (code "81") (name "RESET") (class "Default")
      (node (ref "IC501") (pin "11") (pinfunction "RESET_11") (pintype "input"))
    )
    (net (code "82") (name "R{slash}~{W}") (class "Default")
      (node (ref "IC106") (pin "9") (pinfunction "IN9_9") (pintype "input"))
      (node (ref "IC201") (pin "31") (pinfunction "~{WE}_31") (pintype "input"))
      (node (ref "IC501") (pin "23") (pinfunction "~{WR}_23") (pintype "input"))
      (node (ref "SV101") (pin "12") (pinfunction "12_12") (pintype "passive"))
    )
    (net (code "83") (name "SLOT_D0") (class "Default")
      (node (ref "IC201") (pin "13") (pinfunction "DQ0_13") (pintype "bidirectional"))
      (node (ref "IC501") (pin "22") (pinfunction "D0_22") (pintype "bidirectional"))
    )
    (net (code "84") (name "SLOT_D1") (class "Default")
      (node (ref "IC201") (pin "14") (pinfunction "DQ1_14") (pintype "bidirectional"))
      (node (ref "IC501") (pin "21") (pinfunction "D1_21") (pintype "bidirectional"))
    )
    (net (code "85") (name "SLOT_D2") (class "Default")
      (node (ref "IC201") (pin "15") (pinfunction "DQ2_15") (pintype "bidirectional"))
      (node (ref "IC501") (pin "20") (pinfunction "D2_20") (pintype "bidirectional"))
    )
    (net (code "86") (name "SLOT_D3") (class "Default")
      (node (ref "IC201") (pin "17") (pinfunction "DQ3_17") (pintype "bidirectional"))
      (node (ref "IC501") (pin "19") (pinfunction "D3_19") (pintype "bidirectional"))
    )
    (net (code "87") (name "SLOT_D4") (class "Default")
      (node (ref "IC201") (pin "18") (pinfunction "DQ4_18") (pintype "bidirectional"))
      (node (ref "IC501") (pin "18") (pinfunction "D4_18") (pintype "bidirectional"))
    )
    (net (code "88") (name "SLOT_D5") (class "Default")
      (node (ref "IC201") (pin "19") (pinfunction "DQ5_19") (pintype "bidirectional"))
      (node (ref "IC501") (pin "17") (pinfunction "D5_17") (pintype "bidirectional"))
    )
    (net (code "89") (name "SLOT_D6") (class "Default")
      (node (ref "IC201") (pin "20") (pinfunction "DQ6_20") (pintype "bidirectional"))
      (node (ref "IC501") (pin "16") (pinfunction "D6_16") (pintype "bidirectional"))
    )
    (net (code "90") (name "SLOT_D7") (class "Default")
      (node (ref "IC201") (pin "21") (pinfunction "DQ7_21") (pintype "bidirectional"))
      (node (ref "IC501") (pin "15") (pinfunction "D7_15") (pintype "bidirectional"))
    )
    (net (code "91") (name "UART_CLK") (class "Default")
      (node (ref "IC301") (pin "36") (pinfunction "X1/CLK_36") (pintype "input"))
      (node (ref "IC501") (pin "9") (pinfunction "X1/CLK_9") (pintype "passive"))
      (node (ref "QG101") (pin "5") (pinfunction "OUT_5") (pintype "output"))
    )
    (net (code "92") (name "unconnected-(IC102A-A<B_O-Pad7)") (class "Default")
      (node (ref "IC102") (pin "7") (pinfunction "A<B_O_7") (pintype "output"))
    )
    (net (code "93") (name "unconnected-(IC102A-A>B_O-Pad5)") (class "Default")
      (node (ref "IC102") (pin "5") (pinfunction "A>B_O_5") (pintype "output"))
    )
    (net (code "94") (name "unconnected-(IC105A-Y7-Pad7)") (class "Default")
      (node (ref "IC105") (pin "7") (pinfunction "Y7_7") (pintype "output"))
    )
    (net (code "95") (name "unconnected-(IC106-IN1{slash}CLK-Pad1)") (class "Default")
      (node (ref "IC106") (pin "1") (pinfunction "IN1/CLK_1") (pintype "input"))
    )
    (net (code "96") (name "unconnected-(IC106-IN2-Pad2)") (class "Default")
      (node (ref "IC106") (pin "2") (pinfunction "IN2_2") (pintype "input"))
    )
    (net (code "97") (name "unconnected-(IC106-IN3-Pad3)") (class "Default")
      (node (ref "IC106") (pin "3") (pinfunction "IN3_3") (pintype "input"))
    )
    (net (code "98") (name "unconnected-(IC106-IO18-Pad18)") (class "Default")
      (node (ref "IC106") (pin "18") (pinfunction "IO18_18") (pintype "bidirectional"))
    )
    (net (code "99") (name "unconnected-(IC106-IO19-Pad19)") (class "Default")
      (node (ref "IC106") (pin "19") (pinfunction "IO19_19") (pintype "bidirectional"))
    )
    (net (code "100") (name "unconnected-(IC106-IO20-Pad20)") (class "Default")
      (node (ref "IC106") (pin "20") (pinfunction "IO20_20") (pintype "bidirectional"))
    )
    (net (code "101") (name "unconnected-(IC106-IO21-Pad21)") (class "Default")
      (node (ref "IC106") (pin "21") (pinfunction "IO21_21") (pintype "bidirectional"))
    )
    (net (code "102") (name "unconnected-(IC106-IO23-Pad23)") (class "Default")
      (node (ref "IC106") (pin "23") (pinfunction "IO23_23") (pintype "bidirectional"))
    )
    (net (code "103") (name "unconnected-(IC107A-B2-Pad10)") (class "Default")
      (node (ref "IC107") (pin "10") (pinfunction "B2_10") (pintype "bidirectional"))
    )
    (net (code "104") (name "unconnected-(IC107A-B3-Pad9)") (class "Default")
      (node (ref "IC107") (pin "9") (pinfunction "B3_9") (pintype "bidirectional"))
    )
    (net (code "105") (name "unconnected-(IC107A-B4-Pad8)") (class "Default")
      (node (ref "IC107") (pin "8") (pinfunction "B4_8") (pintype "bidirectional"))
    )
    (net (code "106") (name "unconnected-(IC301-IP0-Pad8)") (class "Default")
      (node (ref "IC301") (pin "8") (pinfunction "IP0_8") (pintype "input"))
    )
    (net (code "107") (name "unconnected-(IC301-IP1-Pad5)") (class "Default")
      (node (ref "IC301") (pin "5") (pinfunction "IP1_5") (pintype "input"))
    )
    (net (code "108") (name "unconnected-(IC301-IP2-Pad40)") (class "Default")
      (node (ref "IC301") (pin "40") (pinfunction "IP2_40") (pintype "input"))
    )
    (net (code "109") (name "unconnected-(IC301-IP3-Pad3)") (class "Default")
      (node (ref "IC301") (pin "3") (pinfunction "IP3_3") (pintype "input"))
    )
    (net (code "110") (name "unconnected-(IC301-IP4-Pad43)") (class "Default")
      (node (ref "IC301") (pin "43") (pinfunction "IP4_43") (pintype "input"))
    )
    (net (code "111") (name "unconnected-(IC301-IP5-Pad42)") (class "Default")
      (node (ref "IC301") (pin "42") (pinfunction "IP5_42") (pintype "input"))
    )
    (net (code "112") (name "unconnected-(IC301-OP0-Pad32)") (class "Default")
      (node (ref "IC301") (pin "32") (pinfunction "OP0_32") (pintype "output"))
    )
    (net (code "113") (name "unconnected-(IC301-OP1-Pad14)") (class "Default")
      (node (ref "IC301") (pin "14") (pinfunction "OP1_14") (pintype "output"))
    )
    (net (code "114") (name "unconnected-(IC301-OP2-Pad31)") (class "Default")
      (node (ref "IC301") (pin "31") (pinfunction "OP2_31") (pintype "output"))
    )
    (net (code "115") (name "unconnected-(IC301-OP3-Pad15)") (class "Default")
      (node (ref "IC301") (pin "15") (pinfunction "OP3_15") (pintype "output"))
    )
    (net (code "116") (name "unconnected-(IC301-OP4-Pad30)") (class "Default")
      (node (ref "IC301") (pin "30") (pinfunction "OP4_30") (pintype "output"))
    )
    (net (code "117") (name "unconnected-(IC301-OP5-Pad16)") (class "Default")
      (node (ref "IC301") (pin "16") (pinfunction "OP5_16") (pintype "output"))
    )
    (net (code "118") (name "unconnected-(IC301-OP6-Pad29)") (class "Default")
      (node (ref "IC301") (pin "29") (pinfunction "OP6_29") (pintype "output"))
    )
    (net (code "119") (name "unconnected-(IC301-OP7-Pad17)") (class "Default")
      (node (ref "IC301") (pin "17") (pinfunction "OP7_17") (pintype "output"))
    )
    (net (code "120") (name "unconnected-(IC301-RXDA-Pad35)") (class "Default")
      (node (ref "IC301") (pin "35") (pinfunction "RXDA_35") (pintype "input"))
    )
    (net (code "121") (name "unconnected-(IC301-RXDB-Pad11)") (class "Default")
      (node (ref "IC301") (pin "11") (pinfunction "RXDB_11") (pintype "output"))
    )
    (net (code "122") (name "unconnected-(IC301-R{slash}~{W}-Pad9)") (class "Default")
      (node (ref "IC301") (pin "9") (pinfunction "R/~{W}_9") (pintype "input"))
    )
    (net (code "123") (name "unconnected-(IC301-TXDA-Pad33)") (class "Default")
      (node (ref "IC301") (pin "33") (pinfunction "TXDA_33") (pintype "output"))
    )
    (net (code "124") (name "unconnected-(IC301-TXDB-Pad13)") (class "Default")
      (node (ref "IC301") (pin "13") (pinfunction "TXDB_13") (pintype "bidirectional"))
    )
    (net (code "125") (name "unconnected-(IC301-X2-Pad37)") (class "Default")
      (node (ref "IC301") (pin "37") (pinfunction "X2_37") (pintype "output"))
    )
    (net (code "126") (name "unconnected-(IC501-A0-Pad8)") (class "Default")
      (node (ref "IC501") (pin "8") (pinfunction "A0_8") (pintype "input"))
    )
    (net (code "127") (name "unconnected-(IC501-A1-Pad7)") (class "Default")
      (node (ref "IC501") (pin "7") (pinfunction "A1_7") (pintype "input"))
    )
    (net (code "128") (name "unconnected-(IC501-A2-Pad6)") (class "Default")
      (node (ref "IC501") (pin "6") (pinfunction "A2_6") (pintype "input"))
    )
    (net (code "129") (name "unconnected-(IC501-MPI-Pad5)") (class "Default")
      (node (ref "IC501") (pin "5") (pinfunction "MPI_5") (pintype "input"))
    )
    (net (code "130") (name "unconnected-(IC501-MPO-Pad4)") (class "Default")
      (node (ref "IC501") (pin "4") (pinfunction "MPO_4") (pintype "output"))
    )
    (net (code "131") (name "unconnected-(IC501-X2-Pad10)") (class "Default")
      (node (ref "IC501") (pin "10") (pinfunction "X2_10") (pintype "passive"))
    )
    (net (code "132") (name "unconnected-(IC502-PB0(ICP)-Pad14)") (class "Default")
      (node (ref "IC502") (pin "14") (pinfunction "PB0(ICP)_14") (pintype "bidirectional"))
    )
    (net (code "133") (name "unconnected-(IC502-PB1(OC1A)-Pad15)") (class "Default")
      (node (ref "IC502") (pin "15") (pinfunction "PB1(OC1A)_15") (pintype "bidirectional"))
    )
    (net (code "134") (name "unconnected-(IC502-PB2(SS{slash}OC1B)-Pad16)") (class "Default")
      (node (ref "IC502") (pin "16") (pinfunction "PB2(SS/OC1B)_16") (pintype "bidirectional"))
    )
    (net (code "135") (name "unconnected-(IC502-PB6(XTAL1{slash}TOSC1)-Pad9)") (class "Default")
      (node (ref "IC502") (pin "9") (pinfunction "PB6(XTAL1/TOSC1)_9") (pintype "bidirectional"))
    )
    (net (code "136") (name "unconnected-(IC502-PB7(XTAL2{slash}TOSC2)-Pad10)") (class "Default")
      (node (ref "IC502") (pin "10") (pinfunction "PB7(XTAL2/TOSC2)_10") (pintype "bidirectional"))
    )
    (net (code "137") (name "unconnected-(IC502-PC0(ADC0)-Pad23)") (class "Default")
      (node (ref "IC502") (pin "23") (pinfunction "PC0(ADC0)_23") (pintype "bidirectional"))
    )
    (net (code "138") (name "unconnected-(IC502-PC1(ADC1)-Pad24)") (class "Default")
      (node (ref "IC502") (pin "24") (pinfunction "PC1(ADC1)_24") (pintype "bidirectional"))
    )
    (net (code "139") (name "unconnected-(IC502-PC2(ADC2)-Pad25)") (class "Default")
      (node (ref "IC502") (pin "25") (pinfunction "PC2(ADC2)_25") (pintype "bidirectional"))
    )
    (net (code "140") (name "unconnected-(IC502-PC3(ADC3)-Pad26)") (class "Default")
      (node (ref "IC502") (pin "26") (pinfunction "PC3(ADC3)_26") (pintype "bidirectional"))
    )
    (net (code "141") (name "unconnected-(IC502-PC4(ADC4{slash}SDA)-Pad27)") (class "Default")
      (node (ref "IC502") (pin "27") (pinfunction "PC4(ADC4/SDA)_27") (pintype "bidirectional"))
    )
    (net (code "142") (name "unconnected-(IC502-PC5(ADC5{slash}SCL)-Pad28)") (class "Default")
      (node (ref "IC502") (pin "28") (pinfunction "PC5(ADC5/SCL)_28") (pintype "bidirectional"))
    )
    (net (code "143") (name "unconnected-(IC502-PD2(INT0)-Pad4)") (class "Default")
      (node (ref "IC502") (pin "4") (pinfunction "PD2(INT0)_4") (pintype "bidirectional"))
    )
    (net (code "144") (name "unconnected-(IC502-PD3(INT1)-Pad5)") (class "Default")
      (node (ref "IC502") (pin "5") (pinfunction "PD3(INT1)_5") (pintype "bidirectional"))
    )
    (net (code "145") (name "unconnected-(IC502-PD4(XCK{slash}T0)-Pad6)") (class "Default")
      (node (ref "IC502") (pin "6") (pinfunction "PD4(XCK/T0)_6") (pintype "bidirectional"))
    )
    (net (code "146") (name "unconnected-(IC502-PD5(T1)-Pad11)") (class "Default")
      (node (ref "IC502") (pin "11") (pinfunction "PD5(T1)_11") (pintype "bidirectional"))
    )
    (net (code "147") (name "unconnected-(IC502-PD6(AIN0)-Pad12)") (class "Default")
      (node (ref "IC502") (pin "12") (pinfunction "PD6(AIN0)_12") (pintype "bidirectional"))
    )
    (net (code "148") (name "unconnected-(IC502-PD7(AIN1)-Pad13)") (class "Default")
      (node (ref "IC502") (pin "13") (pinfunction "PD7(AIN1)_13") (pintype "bidirectional"))
    )
    (net (code "149") (name "unconnected-(QG101-TS-Pad1)") (class "Default")
      (node (ref "QG101") (pin "1") (pinfunction "TS_1") (pintype "passive"))
    )
    (net (code "150") (name "unconnected-(SV101-Pad5)") (class "Default")
      (node (ref "SV101") (pin "5") (pinfunction "5_5") (pintype "passive"))
    )
    (net (code "151") (name "unconnected-(SV101-Pad7)") (class "Default")
      (node (ref "SV101") (pin "7") (pinfunction "7_7") (pintype "passive"))
    )
    (net (code "152") (name "unconnected-(SV101-Pad8)") (class "Default")
      (node (ref "SV101") (pin "8") (pinfunction "8_8") (pintype "passive"))
    )
    (net (code "153") (name "unconnected-(SV101-Pad9)") (class "Default")
      (node (ref "SV101") (pin "9") (pinfunction "9_9") (pintype "passive"))
    )
    (net (code "154") (name "unconnected-(SV101-Pad14)") (class "Default")
      (node (ref "SV101") (pin "14") (pinfunction "14_14") (pintype "passive"))
    )
    (net (code "155") (name "unconnected-(SV101-Pad15)") (class "Default")
      (node (ref "SV101") (pin "15") (pinfunction "15_15") (pintype "passive"))
    )
    (net (code "156") (name "unconnected-(SV101-Pad43)") (class "Default")
      (node (ref "SV101") (pin "43") (pinfunction "43_43") (pintype "passive"))
    )
    (net (code "157") (name "unconnected-(SV101-Pad44)") (class "Default")
      (node (ref "SV101") (pin "44") (pinfunction "44_44") (pintype "passive"))
    )
    (net (code "158") (name "unconnected-(SV101-Pad47)") (class "Default")
      (node (ref "SV101") (pin "47") (pinfunction "47_47") (pintype "passive"))
    )
    (net (code "159") (name "unconnected-(SV101-Pad49)") (class "Default")
      (node (ref "SV101") (pin "49") (pinfunction "49_49") (pintype "passive"))
    )
    (net (code "160") (name "unconnected-(SV101-Pad51)") (class "Default")
      (node (ref "SV101") (pin "51") (pinfunction "51_51") (pintype "passive"))
    )
    (net (code "161") (name "unconnected-(SV101-Pad53)") (class "Default")
      (node (ref "SV101") (pin "53") (pinfunction "53_53") (pintype "passive"))
    )
    (net (code "162") (name "unconnected-(SV101-Pad55)") (class "Default")
      (node (ref "SV101") (pin "55") (pinfunction "55_55") (pintype "passive"))
    )
    (net (code "163") (name "unconnected-(SV101-Pad57)") (class "Default")
      (node (ref "SV101") (pin "57") (pinfunction "57_57") (pintype "passive"))
    )
    (net (code "164") (name "unconnected-(SV101-Pad59)") (class "Default")
      (node (ref "SV101") (pin "59") (pinfunction "59_59") (pintype "passive"))
    )
    (net (code "165") (name "unconnected-(SV101-Pad61)") (class "Default")
      (node (ref "SV101") (pin "61") (pinfunction "61_61") (pintype "passive"))
    )
    (net (code "166") (name "~{68681_IRQ}") (class "Default")
      (node (ref "IC301") (pin "24") (pinfunction "~{INTR}_24") (pintype "output"))
      (node (ref "R303") (pin "1") (pinfunction "1_1") (pintype "passive"))
    )
    (net (code "167") (name "~{AS}") (class "Default")
      (node (ref "IC106") (pin "11") (pinfunction "IN11_11") (pintype "input"))
      (node (ref "SV101") (pin "13") (pinfunction "13_13") (pintype "passive"))
    )
    (net (code "168") (name "~{ATA_CS}") (class "Default")
      (node (ref "IC105") (pin "14") (pinfunction "Y1_14") (pintype "output"))
    )
    (net (code "169") (name "~{AVR_RESET}") (class "Default")
      (node (ref "IC502") (pin "1") (pinfunction "PC6(/RESET)_1") (pintype "bidirectional"))
      (node (ref "SV1") (pin "2") (pinfunction "2_2") (pintype "passive"))
    )
    (net (code "170") (name "~{CS}") (class "Default")
      (node (ref "IC101") (pin "19") (pinfunction "G_19") (pintype "input"))
      (node (ref "IC103") (pin "19") (pinfunction "G_19") (pintype "input"))
      (node (ref "IC104") (pin "19") (pinfunction "G_19") (pintype "input"))
      (node (ref "IC105") (pin "4") (pinfunction "G2A_4") (pintype "input"))
      (node (ref "IC106") (pin "14") (pinfunction "IO14_14") (pintype "bidirectional"))
      (node (ref "IC107") (pin "1") (pinfunction "GAB_1") (pintype "input"))
    )
    (net (code "171") (name "~{DTACK}") (class "Default")
      (node (ref "IC106") (pin "16") (pinfunction "IO16_16") (pintype "bidirectional"))
      (node (ref "IC301") (pin "10") (pinfunction "~{DTACK}_10") (pintype "output"))
      (node (ref "SV101") (pin "10") (pinfunction "10_10") (pintype "passive"))
    )
    (net (code "172") (name "~{DUART_CS}") (class "Default")
      (node (ref "IC105") (pin "15") (pinfunction "Y0_15") (pintype "output"))
      (node (ref "IC301") (pin "39") (pinfunction "~{CS}_39") (pintype "input"))
    )
    (net (code "173") (name "~{EXTI_A}") (class "Default")
      (node (ref "IC106") (pin "17") (pinfunction "IO17_17") (pintype "bidirectional"))
      (node (ref "SV101") (pin "16") (pinfunction "16_16") (pintype "passive"))
    )
    (net (code "174") (name "~{EXT_ID}") (class "Default")
      (node (ref "IC106") (pin "6") (pinfunction "IN6_6") (pintype "input"))
      (node (ref "SV101") (pin "41") (pinfunction "41_41") (pintype "passive"))
    )
    (net (code "175") (name "~{I2C_CS}") (class "Default")
      (node (ref "IC105") (pin "9") (pinfunction "Y6_9") (pintype "output"))
    )
    (net (code "176") (name "~{LCD_CS}") (class "Default")
      (node (ref "IC105") (pin "11") (pinfunction "Y4_11") (pintype "output"))
    )
    (net (code "177") (name "~{LDS}") (class "Default")
      (node (ref "IC106") (pin "10") (pinfunction "IN10_10") (pintype "input"))
      (node (ref "SV101") (pin "11") (pinfunction "11_11") (pintype "passive"))
    )
    (net (code "178") (name "~{PIO_CS}") (class "Default")
      (node (ref "IC105") (pin "12") (pinfunction "Y3_12") (pintype "output"))
    )
    (net (code "179") (name "~{PS2_CS}") (class "Default")
      (node (ref "IC105") (pin "13") (pinfunction "Y2_13") (pintype "output"))
      (node (ref "IC501") (pin "14") (pinfunction "~{CS}_14") (pintype "input"))
    )
    (net (code "180") (name "~{PS2_IRQ}") (class "Default")
      (node (ref "IC501") (pin "13") (pinfunction "~{IRQ}_13") (pintype "output"))
    )
    (net (code "181") (name "~{RD}") (class "Default")
      (node (ref "IC101") (pin "1") (pinfunction "DIR_1") (pintype "input"))
      (node (ref "IC106") (pin "15") (pinfunction "IO15_15") (pintype "bidirectional"))
      (node (ref "IC201") (pin "24") (pinfunction "~{OE}_24") (pintype "input"))
      (node (ref "IC501") (pin "1") (pinfunction "~{RD}_1") (pintype "input"))
    )
    (net (code "182") (name "~{RESET}") (class "Default")
      (node (ref "IC106") (pin "8") (pinfunction "IN8_8") (pintype "input"))
      (node (ref "IC301") (pin "38") (pinfunction "~{RESET}_38") (pintype "input"))
      (node (ref "SV101") (pin "6") (pinfunction "6_6") (pintype "passive"))
    )
    (net (code "183") (name "~{ROM_CS}") (class "Default")
      (node (ref "IC105") (pin "6") (pinfunction "G1_6") (pintype "input"))
      (node (ref "IC106") (pin "22") (pinfunction "IO22_22") (pintype "bidirectional"))
      (node (ref "IC201") (pin "22") (pinfunction "~{CS}_22") (pintype "input"))
    )
    (net (code "184") (name "~{STATUS_CS}") (class "Default")
      (node (ref "IC105") (pin "10") (pinfunction "Y5_10") (pintype "output"))
    )
  )
)
